# 555_rfm95w_breakout_v2_1.net
KiCad netlist of a schematic drawn in EAGLE
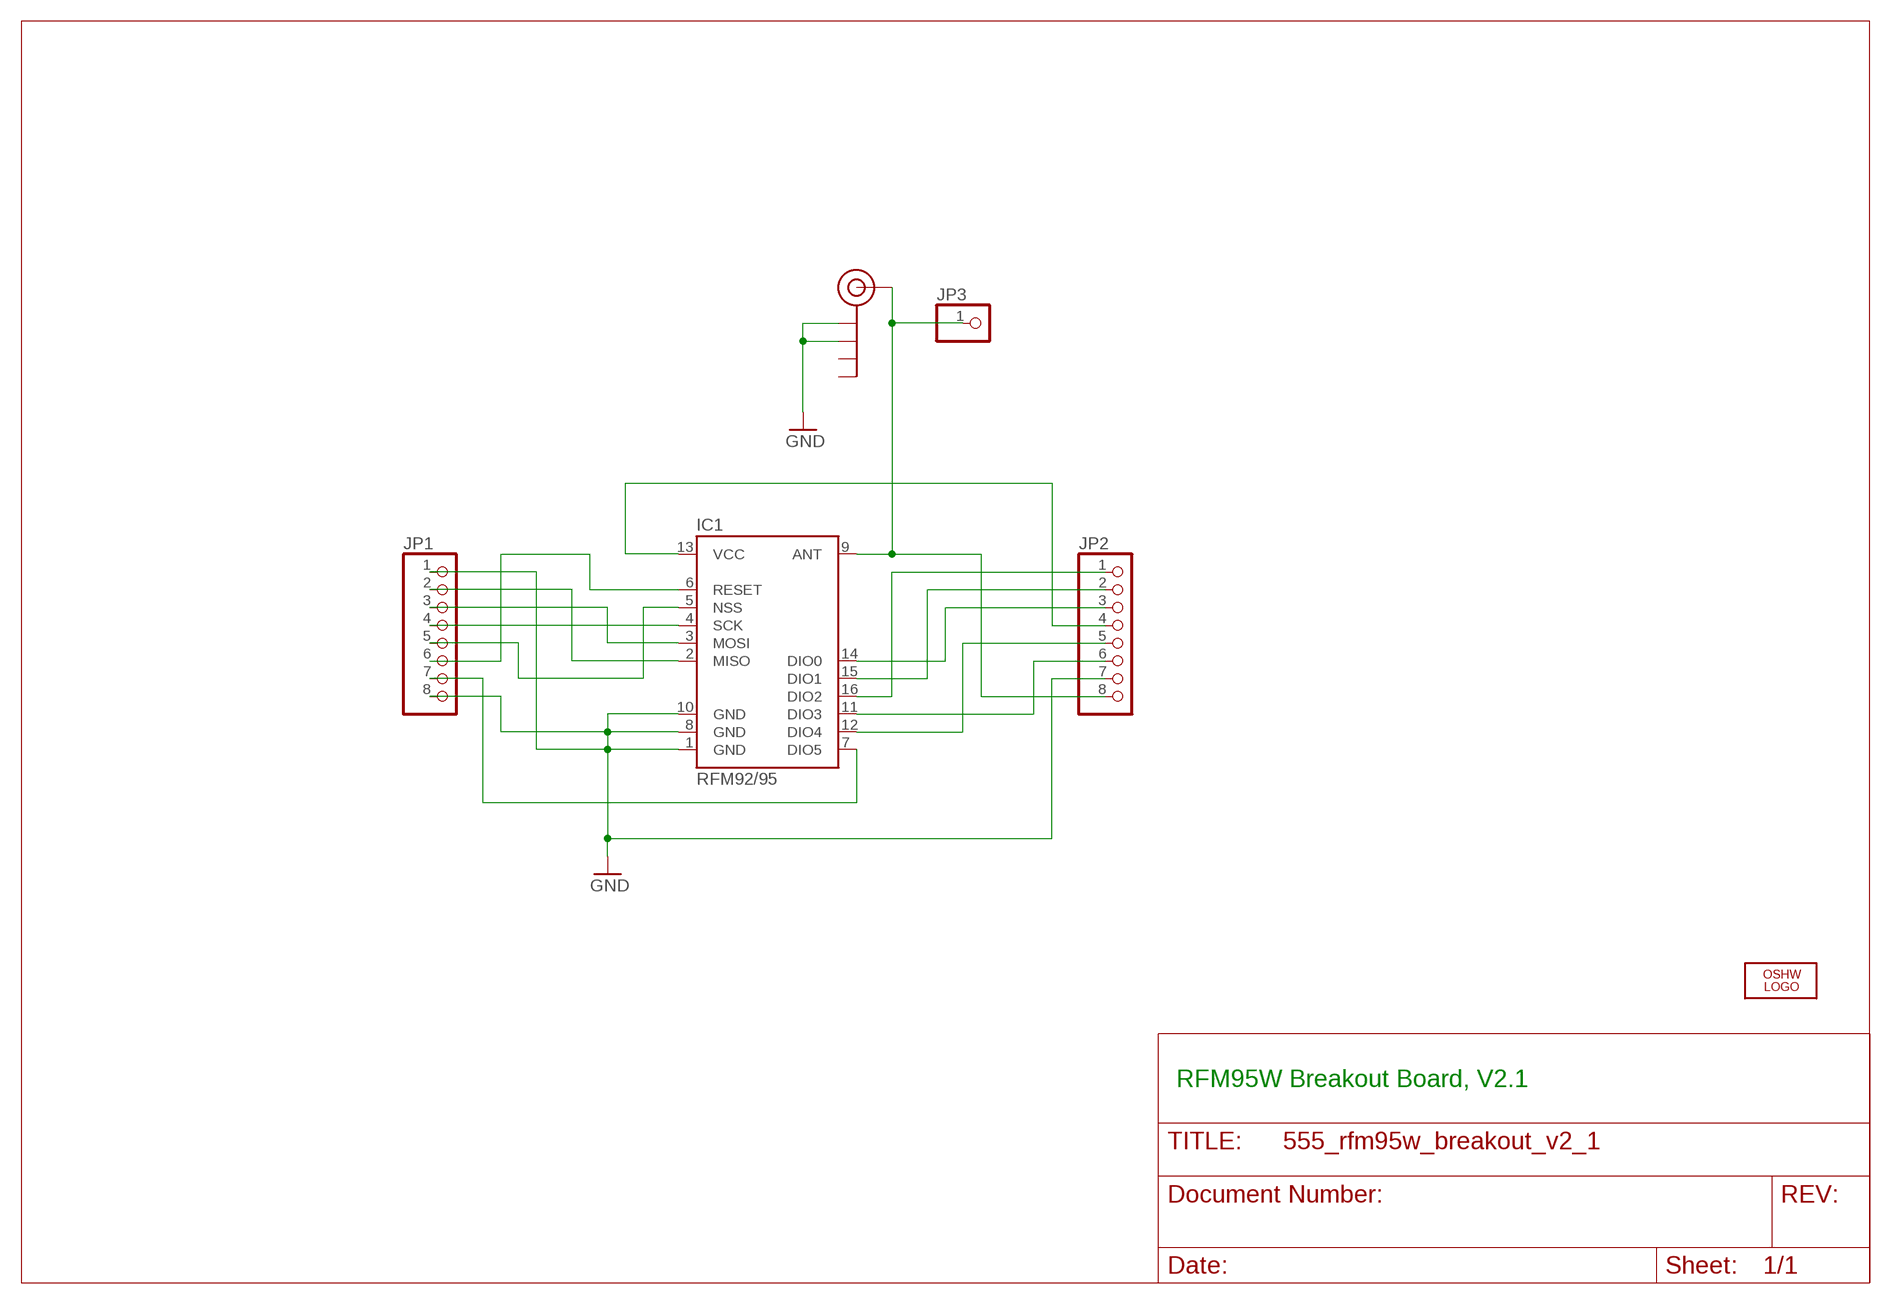
[diagram p0: schematic, sheet 1]

(export (version "E")
  (design (tool "Eeschema 10.0.6"))
  (components
    (comp (ref "IC1")
      (value "RFM92/95")
      (footprint "eagle-import:RFM95W_SMD")
      (libsource (lib "eagle-import") (part "RFM95WSMD"))
    )
    (comp (ref "J$1")
      (value "ANT")
      (footprint "eagle-import:SMA_EDGE")
      (libsource (lib "eagle-import") (part "SMA_EDGE"))
    )
    (comp (ref "JP1")
      (value "PINHD-1X8")
      (footprint "eagle-import:1X08")
      (libsource (lib "eagle-import") (part "PINHD-1X8"))
    )
    (comp (ref "JP2")
      (value "PINHD-1X8")
      (footprint "eagle-import:1X08")
      (libsource (lib "eagle-import") (part "PINHD-1X8"))
    )
    (comp (ref "JP3")
      (value "PINHD-1X1")
      (footprint "eagle-import:1X01")
      (libsource (lib "eagle-import") (part "PINHD-1X1"))
    )
    (comp (ref "LOGO1")
      (value "OSHW_LOGO_FILLX0100-NT")
      (footprint "eagle-import:OSHW_FILLX100_NOTEXT")
      (libsource (lib "eagle-import") (part "OSHW_LOGO_FILLX0100-NT"))
    )
  )
  (nets
    (net (code "1") (name "GND") (class "Default")
      (node (ref "IC1") (pin "1") (pinfunction "GND_1") (pintype "power_in"))
      (node (ref "IC1") (pin "10") (pinfunction "GND_10") (pintype "power_in"))
      (node (ref "IC1") (pin "8") (pinfunction "GND_8") (pintype "power_in"))
      (node (ref "J$1") (pin "GND@0") (pinfunction "GND_GND@0") (pintype "bidirectional"))
      (node (ref "J$1") (pin "GND@1") (pinfunction "GND_GND@1") (pintype "bidirectional"))
      (node (ref "JP1") (pin "1") (pinfunction "1_1") (pintype "passive"))
      (node (ref "JP1") (pin "8") (pinfunction "8_8") (pintype "passive"))
      (node (ref "JP2") (pin "7") (pinfunction "7_7") (pintype "passive"))
    )
    (net (code "2") (name "Net-(IC1-ANT)") (class "Default")
      (node (ref "IC1") (pin "9") (pinfunction "ANT_9") (pintype "bidirectional"))
      (node (ref "J$1") (pin "SIG") (pinfunction "SIGNAL_SIG") (pintype "bidirectional"))
      (node (ref "JP2") (pin "8") (pinfunction "8_8") (pintype "passive"))
      (node (ref "JP3") (pin "1") (pinfunction "1_1") (pintype "passive"))
    )
    (net (code "3") (name "Net-(IC1-DIO0)") (class "Default")
      (node (ref "IC1") (pin "14") (pinfunction "DIO0_14") (pintype "input"))
      (node (ref "JP2") (pin "3") (pinfunction "3_3") (pintype "passive"))
    )
    (net (code "4") (name "Net-(IC1-DIO1)") (class "Default")
      (node (ref "IC1") (pin "15") (pinfunction "DIO1_15") (pintype "input"))
      (node (ref "JP2") (pin "2") (pinfunction "2_2") (pintype "passive"))
    )
    (net (code "5") (name "Net-(IC1-DIO2)") (class "Default")
      (node (ref "IC1") (pin "16") (pinfunction "DIO2_16") (pintype "input"))
      (node (ref "JP2") (pin "1") (pinfunction "1_1") (pintype "passive"))
    )
    (net (code "6") (name "Net-(IC1-DIO3)") (class "Default")
      (node (ref "IC1") (pin "11") (pinfunction "DIO3_11") (pintype "bidirectional"))
      (node (ref "JP2") (pin "6") (pinfunction "6_6") (pintype "passive"))
    )
    (net (code "7") (name "Net-(IC1-DIO4)") (class "Default")
      (node (ref "IC1") (pin "12") (pinfunction "DIO4_12") (pintype "bidirectional"))
      (node (ref "JP2") (pin "5") (pinfunction "5_5") (pintype "passive"))
    )
    (net (code "8") (name "Net-(IC1-DIO5)") (class "Default")
      (node (ref "IC1") (pin "7") (pinfunction "DIO5_7") (pintype "bidirectional"))
      (node (ref "JP1") (pin "7") (pinfunction "7_7") (pintype "passive"))
    )
    (net (code "9") (name "Net-(IC1-MISO)") (class "Default")
      (node (ref "IC1") (pin "2") (pinfunction "MISO_2") (pintype "output"))
      (node (ref "JP1") (pin "2") (pinfunction "2_2") (pintype "passive"))
    )
    (net (code "10") (name "Net-(IC1-MOSI)") (class "Default")
      (node (ref "IC1") (pin "3") (pinfunction "MOSI_3") (pintype "input"))
      (node (ref "JP1") (pin "3") (pinfunction "3_3") (pintype "passive"))
    )
    (net (code "11") (name "Net-(IC1-NSS)") (class "Default")
      (node (ref "IC1") (pin "5") (pinfunction "NSS_5") (pintype "input"))
      (node (ref "JP1") (pin "5") (pinfunction "5_5") (pintype "passive"))
    )
    (net (code "12") (name "Net-(IC1-RESET)") (class "Default")
      (node (ref "IC1") (pin "6") (pinfunction "RESET_6") (pintype "output"))
      (node (ref "JP1") (pin "6") (pinfunction "6_6") (pintype "passive"))
    )
    (net (code "13") (name "Net-(IC1-SCK)") (class "Default")
      (node (ref "IC1") (pin "4") (pinfunction "SCK_4") (pintype "input"))
      (node (ref "JP1") (pin "4") (pinfunction "4_4") (pintype "passive"))
    )
    (net (code "14") (name "Net-(IC1-VCC)") (class "Default")
      (node (ref "IC1") (pin "13") (pinfunction "VCC_13") (pintype "bidirectional"))
      (node (ref "JP2") (pin "4") (pinfunction "4_4") (pintype "passive"))
    )
    (net (code "15") (name "unconnected-(J$1-GND-PadGND@2)") (class "Default")
      (node (ref "J$1") (pin "GND@2") (pinfunction "GND_GND@2") (pintype "bidirectional"))
    )
    (net (code "16") (name "unconnected-(J$1-GND-PadGND@3)") (class "Default")
      (node (ref "J$1") (pin "GND@3") (pinfunction "GND_GND@3") (pintype "bidirectional"))
    )
  )
)
